# dcmotor.net
KiCad netlist of a schematic drawn in EAGLE
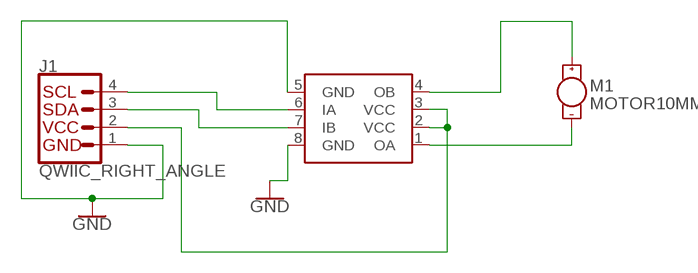
[diagram p0: schematic, sheet 1]

(export (version "E")
  (design (tool "Eeschema 10.0.6"))
  (components
    (comp (ref "J1")
      (value "QWIIC_RIGHT_ANGLE")
      (footprint "eagle-import:JST04_1MM_RA")
      (libsource (lib "eagle-import") (part "QWIIC_CONNECTORJS-1MM"))
    )
    (comp (ref "M1")
      (value "MOTOR10MM")
      (footprint "eagle-import:VIBE-MOTOR-10MM")
      (libsource (lib "eagle-import") (part "MOTOR10MM"))
    )
    (comp (ref "U$1")
      (value "L9110SO8")
      (footprint "eagle-import:SO-08")
      (fields (field (name "MF") "Asic") (field (name "MP") "L9110 (SOP-8)"))
      (libsource (lib "eagle-import") (part "L9110SO8"))
    )
  )
  (nets
    (net (code "1") (name "GND") (class "Default")
      (node (ref "J1") (pin "1") (pinfunction "1_1") (pintype "power_in"))
      (node (ref "U$1") (pin "5") (pinfunction "GND_5") (pintype "power_in"))
      (node (ref "U$1") (pin "8") (pinfunction "GND_8") (pintype "power_in"))
    )
    (net (code "2") (name "Net-(J1-Pad2)") (class "Default")
      (node (ref "J1") (pin "2") (pinfunction "2_2") (pintype "power_in"))
      (node (ref "U$1") (pin "2") (pinfunction "VCC_2") (pintype "power_in"))
      (node (ref "U$1") (pin "3") (pinfunction "VCC_3") (pintype "power_in"))
    )
    (net (code "3") (name "Net-(U$1-IA)") (class "Default")
      (node (ref "J1") (pin "4") (pinfunction "4_4") (pintype "passive"))
      (node (ref "U$1") (pin "6") (pinfunction "IA_6") (pintype "input"))
    )
    (net (code "4") (name "Net-(U$1-IB)") (class "Default")
      (node (ref "J1") (pin "3") (pinfunction "3_3") (pintype "passive"))
      (node (ref "U$1") (pin "7") (pinfunction "IB_7") (pintype "input"))
    )
    (net (code "5") (name "Net-(U$1-OA)") (class "Default")
      (node (ref "M1") (pin "-") (pinfunction "-_-") (pintype "bidirectional"))
      (node (ref "U$1") (pin "1") (pinfunction "OA_1") (pintype "output"))
    )
    (net (code "6") (name "Net-(U$1-OB)") (class "Default")
      (node (ref "M1") (pin "+") (pinfunction "+_+") (pintype "bidirectional"))
      (node (ref "U$1") (pin "4") (pinfunction "OB_4") (pintype "output"))
    )
  )
)
